# Ultrasonic_Module_V1_1.net
KiCad netlist of a schematic drawn in Altium Designer
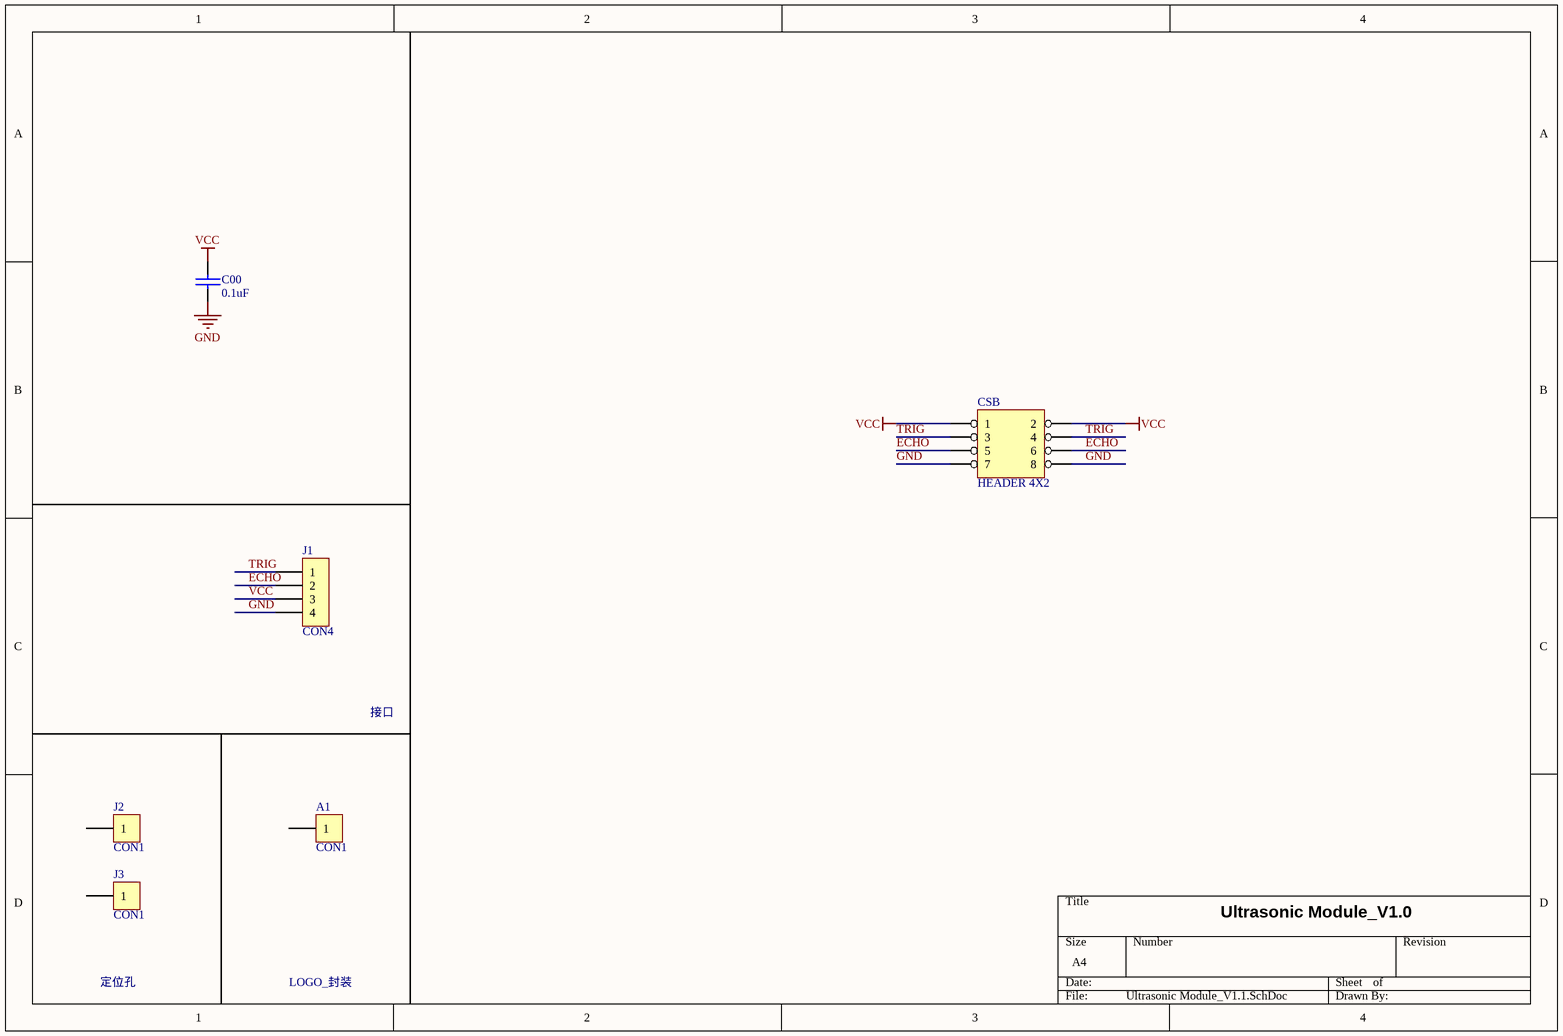
[diagram p0: Ultrasonic Module_V1.1.SchDoc]

(export (version "E")
  (design (tool "Eeschema 10.0.6"))
  (components
    (comp (ref "A1")
      (value "CON1")
      (footprint "GD32LOGO")
      (description "Connector")
      (libsource (lib "Protel99Lib_SCH") (part "CON1"))
    )
    (comp (ref "C00")
      (value "0.1uF")
      (footprint "0805C")
      (description "Capacitor")
      (libsource (lib "Protel99Lib_SCH") (part "CAP"))
    )
    (comp (ref "CSB")
      (value "HEADER 4X2")
      (footprint "IDC8-JLC")
      (libsource (lib "Protel99Lib_SCH") (part "HEADER 4X2"))
    )
    (comp (ref "J1")
      (value "CON4")
      (footprint "SIP4")
      (description "Connector")
      (libsource (lib "Protel99Lib_SCH") (part "CON4"))
    )
    (comp (ref "J2")
      (value "CON1")
      (footprint "HOLE-4.8")
      (description "Connector")
      (libsource (lib "Protel99Lib_SCH") (part "CON1"))
    )
    (comp (ref "J3")
      (value "CON1")
      (footprint "HOLE-4.8")
      (description "Connector")
      (libsource (lib "Protel99Lib_SCH") (part "CON1"))
    )
  )
  (nets
    (net (code "1") (name "/ECHO") (class "Default")
      (node (ref "CSB") (pin "5") (pinfunction "5_5") (pintype "passive"))
      (node (ref "CSB") (pin "6") (pinfunction "6_6") (pintype "passive"))
      (node (ref "J1") (pin "2") (pinfunction "2_2") (pintype "passive"))
    )
    (net (code "2") (name "/TRIG") (class "Default")
      (node (ref "CSB") (pin "3") (pinfunction "3_3") (pintype "passive"))
      (node (ref "CSB") (pin "4") (pinfunction "4_4") (pintype "passive"))
      (node (ref "J1") (pin "1") (pinfunction "1_1") (pintype "passive"))
    )
    (net (code "3") (name "GND") (class "Default")
      (node (ref "C00") (pin "2") (pinfunction "2_2") (pintype "passive"))
      (node (ref "CSB") (pin "7") (pinfunction "7_7") (pintype "passive"))
      (node (ref "CSB") (pin "8") (pinfunction "8_8") (pintype "passive"))
      (node (ref "J1") (pin "4") (pinfunction "4_4") (pintype "passive"))
    )
    (net (code "4") (name "VCC") (class "Default")
      (node (ref "C00") (pin "1") (pinfunction "1_1") (pintype "passive"))
      (node (ref "CSB") (pin "1") (pinfunction "1_1") (pintype "passive"))
      (node (ref "CSB") (pin "2") (pinfunction "2_2") (pintype "passive"))
      (node (ref "J1") (pin "3") (pinfunction "3_3") (pintype "passive"))
    )
    (net (code "5") (name "unconnected-(A1-Pad1)") (class "Default")
      (node (ref "A1") (pin "1") (pinfunction "1_1") (pintype "passive"))
    )
    (net (code "6") (name "unconnected-(J2-Pad1)") (class "Default")
      (node (ref "J2") (pin "1") (pinfunction "1_1") (pintype "passive"))
    )
    (net (code "7") (name "unconnected-(J3-Pad1)") (class "Default")
      (node (ref "J3") (pin "1") (pinfunction "1_1") (pintype "passive"))
    )
  )
)
